# seven-segment-helper-board.net
KiCad netlist of a schematic drawn in EAGLE
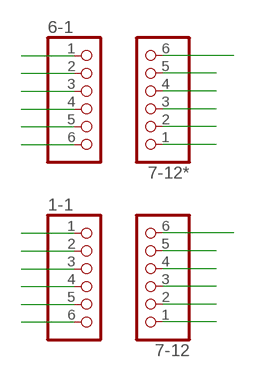
[diagram p0: schematic, sheet 1]

(export (version "E")
  (design (tool "Eeschema 10.0.6"))
  (components
    (comp (ref "1-1")
      (value "PINHD-1X6")
      (footprint "eagle-import:1X06")
      (libsource (lib "eagle-import") (part "PINHD-1X6"))
    )
    (comp (ref "6-1")
      (value "PINHD-1X6")
      (footprint "eagle-import:1X06")
      (libsource (lib "eagle-import") (part "PINHD-1X6"))
    )
    (comp (ref "7-12")
      (value "PINHD-1X6")
      (footprint "eagle-import:1X06")
      (libsource (lib "eagle-import") (part "PINHD-1X6"))
    )
    (comp (ref "7-12*")
      (value "PINHD-1X6")
      (footprint "eagle-import:1X06")
      (libsource (lib "eagle-import") (part "PINHD-1X6"))
    )
  )
  (nets
    (net (code "1") (name "/1") (class "Default")
      (node (ref "1-1") (pin "1") (pinfunction "1_1") (pintype "passive"))
      (node (ref "6-1") (pin "1") (pinfunction "1_1") (pintype "passive"))
    )
    (net (code "2") (name "/2") (class "Default")
      (node (ref "1-1") (pin "2") (pinfunction "2_2") (pintype "passive"))
      (node (ref "6-1") (pin "2") (pinfunction "2_2") (pintype "passive"))
    )
    (net (code "3") (name "/3") (class "Default")
      (node (ref "1-1") (pin "3") (pinfunction "3_3") (pintype "passive"))
      (node (ref "6-1") (pin "3") (pinfunction "3_3") (pintype "passive"))
    )
    (net (code "4") (name "/4") (class "Default")
      (node (ref "1-1") (pin "4") (pinfunction "4_4") (pintype "passive"))
      (node (ref "6-1") (pin "4") (pinfunction "4_4") (pintype "passive"))
    )
    (net (code "5") (name "/5") (class "Default")
      (node (ref "1-1") (pin "5") (pinfunction "5_5") (pintype "passive"))
      (node (ref "6-1") (pin "5") (pinfunction "5_5") (pintype "passive"))
    )
    (net (code "6") (name "/6") (class "Default")
      (node (ref "1-1") (pin "6") (pinfunction "6_6") (pintype "passive"))
      (node (ref "6-1") (pin "6") (pinfunction "6_6") (pintype "passive"))
    )
    (net (code "7") (name "/7") (class "Default")
      (node (ref "7-12") (pin "1") (pinfunction "1_1") (pintype "passive"))
      (node (ref "7-12*") (pin "1") (pinfunction "1_1") (pintype "passive"))
    )
    (net (code "8") (name "/8") (class "Default")
      (node (ref "7-12") (pin "2") (pinfunction "2_2") (pintype "passive"))
      (node (ref "7-12*") (pin "2") (pinfunction "2_2") (pintype "passive"))
    )
    (net (code "9") (name "/9") (class "Default")
      (node (ref "7-12") (pin "3") (pinfunction "3_3") (pintype "passive"))
      (node (ref "7-12*") (pin "3") (pinfunction "3_3") (pintype "passive"))
    )
    (net (code "10") (name "/10") (class "Default")
      (node (ref "7-12") (pin "4") (pinfunction "4_4") (pintype "passive"))
      (node (ref "7-12*") (pin "4") (pinfunction "4_4") (pintype "passive"))
    )
    (net (code "11") (name "/11") (class "Default")
      (node (ref "7-12") (pin "5") (pinfunction "5_5") (pintype "passive"))
      (node (ref "7-12*") (pin "5") (pinfunction "5_5") (pintype "passive"))
    )
    (net (code "12") (name "/12") (class "Default")
      (node (ref "7-12") (pin "6") (pinfunction "6_6") (pintype "passive"))
      (node (ref "7-12*") (pin "6") (pinfunction "6_6") (pintype "passive"))
    )
  )
)
